# VCO3340_v2.net
KiCad netlist of a schematic drawn in EAGLE
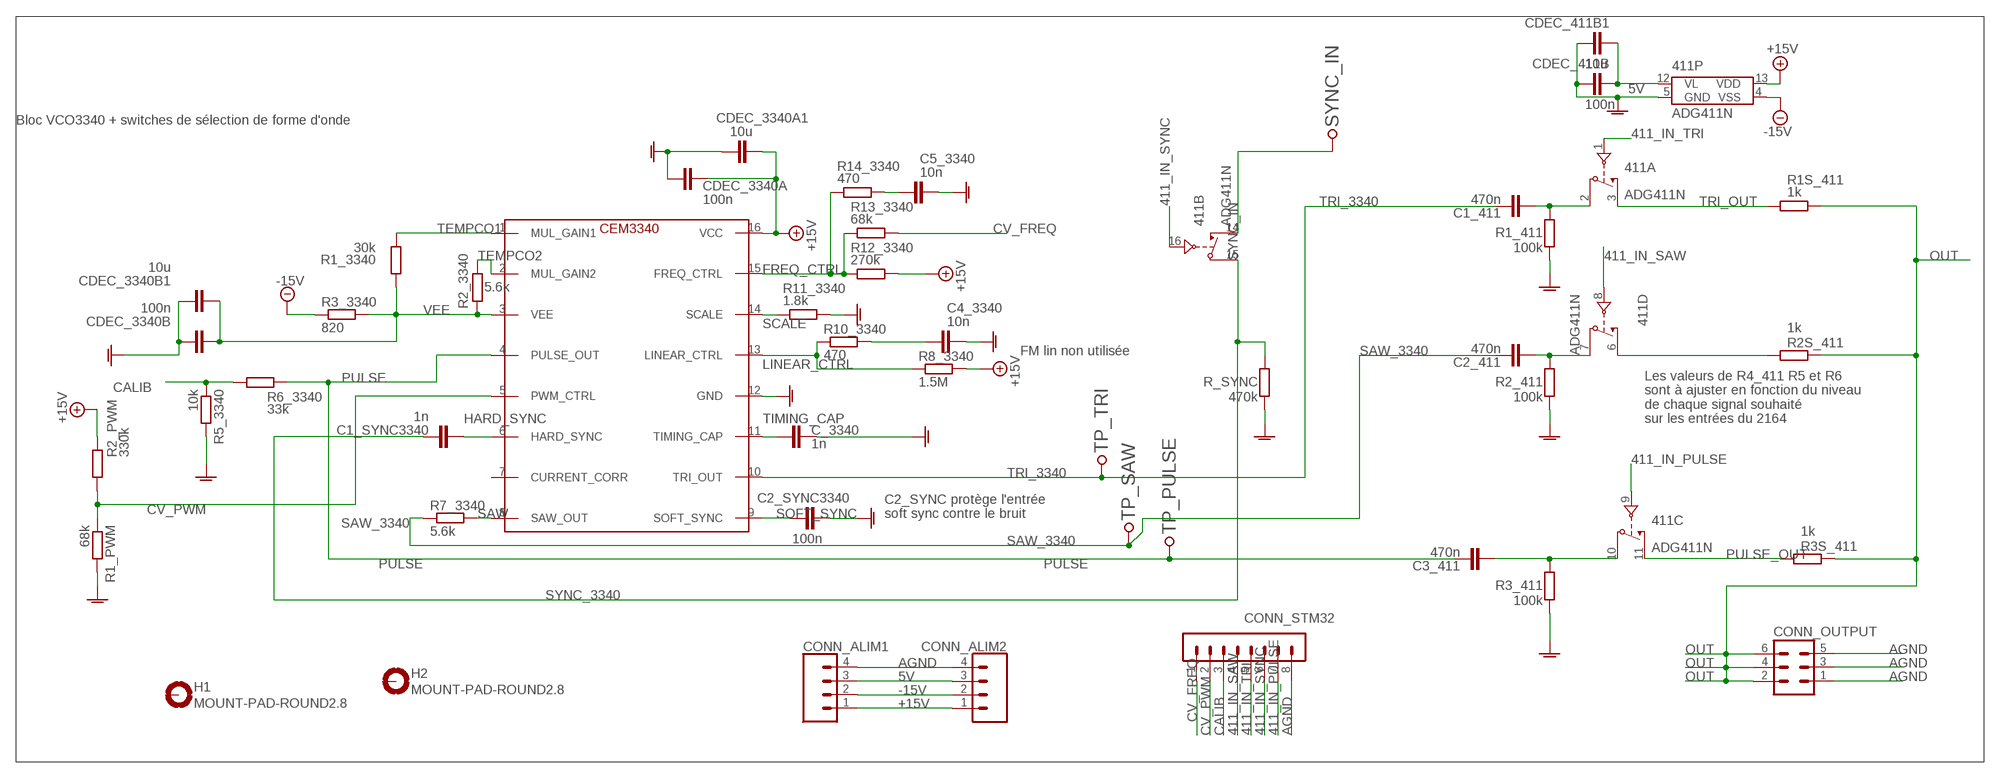
[diagram p0: schematic, sheet 1]

(export (version "E")
  (design (tool "Eeschema 10.0.6"))
  (components
    (comp (ref "411")
      (value "ADG411N")
      (footprint "eagle-import:DIL16")
      (fields (field (name "MF") "ALTERA CORPORATION") (field (name "MPN") "ADG411BN"))
      (libsource (lib "eagle-import") (part "ADG411N"))
    )
    (comp (ref "C1_411")
      (value "470n")
      (footprint "eagle-import:C075-032X103")
      (libsource (lib "eagle-import") (part "C-EU075-032X103"))
    )
    (comp (ref "C1_SYNC3340")
      (value "1n")
      (footprint "eagle-import:C075-032X103")
      (libsource (lib "eagle-import") (part "C-EU075-032X103"))
    )
    (comp (ref "C2_411")
      (value "470n")
      (footprint "eagle-import:C075-032X103")
      (libsource (lib "eagle-import") (part "C-EU075-032X103"))
    )
    (comp (ref "C2_SYNC3340")
      (value "100n")
      (footprint "eagle-import:C075-032X103")
      (libsource (lib "eagle-import") (part "C-EU075-032X103"))
    )
    (comp (ref "C3_411")
      (value "470n")
      (footprint "eagle-import:C102-043X133")
      (libsource (lib "eagle-import") (part "C-EU102-043X133"))
    )
    (comp (ref "C4_3340")
      (value "10n")
      (footprint "eagle-import:C050-025X075")
      (libsource (lib "eagle-import") (part "C-EU050-025X075"))
    )
    (comp (ref "C5_3340")
      (value "10n")
      (footprint "eagle-import:C075-032X103")
      (libsource (lib "eagle-import") (part "C-EU075-032X103"))
    )
    (comp (ref "CDEC_411B")
      (value "100n")
      (footprint "eagle-import:C050-025X075")
      (libsource (lib "eagle-import") (part "C-EU050-025X075"))
    )
    (comp (ref "CDEC_411B1")
      (value "10u")
      (footprint "eagle-import:C050-025X075")
      (libsource (lib "eagle-import") (part "C-EU050-025X075"))
    )
    (comp (ref "CDEC_3340A")
      (value "100n")
      (footprint "eagle-import:C050-025X075")
      (libsource (lib "eagle-import") (part "C-EU050-025X075"))
    )
    (comp (ref "CDEC_3340A1")
      (value "10u")
      (footprint "eagle-import:C050-025X075")
      (libsource (lib "eagle-import") (part "C-EU050-025X075"))
    )
    (comp (ref "CDEC_3340B")
      (value "100n")
      (footprint "eagle-import:C050-025X075")
      (libsource (lib "eagle-import") (part "C-EU050-025X075"))
    )
    (comp (ref "CDEC_3340B1")
      (value "10u")
      (footprint "eagle-import:C050-025X075")
      (libsource (lib "eagle-import") (part "C-EU050-025X075"))
    )
    (comp (ref "CEM3340")
      (value "CEM3340")
      (footprint "eagle-import:DIL16")
      (libsource (lib "eagle-import") (part "CEM3340"))
    )
    (comp (ref "CONN_ALIM1")
      (value "CONN_04")
      (footprint "eagle-import:1X04")
      (libsource (lib "eagle-import") (part "CONN_04"))
    )
    (comp (ref "CONN_ALIM2")
      (value "CONN_04")
      (footprint "eagle-import:1X04")
      (libsource (lib "eagle-import") (part "CONN_04"))
    )
    (comp (ref "CONN_OUTPUT")
      (value "MA03-2")
      (footprint "eagle-import:MA03-2")
      (libsource (lib "eagle-import") (part "MA03-2"))
    )
    (comp (ref "CONN_STM32")
      (value "MA08-1")
      (footprint "eagle-import:MA08-1")
      (libsource (lib "eagle-import") (part "MA08-1"))
    )
    (comp (ref "C_3340")
      (value "1n")
      (footprint "eagle-import:C050-025X075")
      (libsource (lib "eagle-import") (part "C-EU050-025X075"))
    )
    (comp (ref "H1")
      (value "MOUNT-PAD-ROUND2.8")
      (footprint "eagle-import:2,8-PAD")
      (libsource (lib "eagle-import") (part "MOUNT-PAD-ROUND2.8"))
    )
    (comp (ref "H2")
      (value "MOUNT-PAD-ROUND2.8")
      (footprint "eagle-import:2,8-PAD")
      (libsource (lib "eagle-import") (part "MOUNT-PAD-ROUND2.8"))
    )
    (comp (ref "R1S_411")
      (value "1k")
      (footprint "eagle-import:0204_7")
      (libsource (lib "eagle-import") (part "R-EU_0204/7"))
    )
    (comp (ref "R1_411")
      (value "100k")
      (footprint "eagle-import:0207_10")
      (libsource (lib "eagle-import") (part "R-EU_0207/10"))
    )
    (comp (ref "R1_3340")
      (value "30k")
      (footprint "eagle-import:0204_7")
      (libsource (lib "eagle-import") (part "R-EU_0204/7"))
    )
    (comp (ref "R1_PWM")
      (value "68k")
      (footprint "eagle-import:0207_12")
      (libsource (lib "eagle-import") (part "R-EU_0207/12"))
    )
    (comp (ref "R2S_411")
      (value "1k")
      (footprint "eagle-import:0207_10")
      (libsource (lib "eagle-import") (part "R-EU_0207/10"))
    )
    (comp (ref "R2_411")
      (value "100k")
      (footprint "eagle-import:0207_10")
      (libsource (lib "eagle-import") (part "R-EU_0207/10"))
    )
    (comp (ref "R2_3340")
      (value "5.6k")
      (footprint "eagle-import:0204_7")
      (libsource (lib "eagle-import") (part "R-EU_0204/7"))
    )
    (comp (ref "R2_PWM")
      (value "330k")
      (footprint "eagle-import:0204_7")
      (libsource (lib "eagle-import") (part "R-EU_0204/7"))
    )
    (comp (ref "R3S_411")
      (value "1k")
      (footprint "eagle-import:0204_7")
      (libsource (lib "eagle-import") (part "R-EU_0204/7"))
    )
    (comp (ref "R3_411")
      (value "100k")
      (footprint "eagle-import:0204_7")
      (libsource (lib "eagle-import") (part "R-EU_0204/7"))
    )
    (comp (ref "R3_3340")
      (value "820")
      (footprint "eagle-import:0204_7")
      (libsource (lib "eagle-import") (part "R-EU_0204/7"))
    )
    (comp (ref "R5_3340")
      (value "10k")
      (footprint "eagle-import:0204_7")
      (libsource (lib "eagle-import") (part "R-EU_0204/7"))
    )
    (comp (ref "R6_3340")
      (value "33k")
      (footprint "eagle-import:0204_7")
      (libsource (lib "eagle-import") (part "R-EU_0204/7"))
    )
    (comp (ref "R7_3340")
      (value "5.6k")
      (footprint "eagle-import:0207_10")
      (libsource (lib "eagle-import") (part "R-EU_0207/10"))
    )
    (comp (ref "R8_3340")
      (value "1.5M")
      (footprint "eagle-import:0204_7")
      (libsource (lib "eagle-import") (part "R-EU_0204/7"))
    )
    (comp (ref "R10_3340")
      (value "470")
      (footprint "eagle-import:0204_7")
      (libsource (lib "eagle-import") (part "R-EU_0204/7"))
    )
    (comp (ref "R11_3340")
      (value "1.8k")
      (footprint "eagle-import:0204_7")
      (libsource (lib "eagle-import") (part "R-EU_0204/7"))
    )
    (comp (ref "R12_3340")
      (value "270k")
      (footprint "eagle-import:0204_7")
      (libsource (lib "eagle-import") (part "R-EU_0204/7"))
    )
    (comp (ref "R13_3340")
      (value "68k")
      (footprint "eagle-import:0204_7")
      (libsource (lib "eagle-import") (part "R-EU_0204/7"))
    )
    (comp (ref "R14_3340")
      (value "470")
      (footprint "eagle-import:0204_7")
      (libsource (lib "eagle-import") (part "R-EU_0204/7"))
    )
    (comp (ref "R_SYNC")
      (value "470k")
      (footprint "eagle-import:0204_7")
      (libsource (lib "eagle-import") (part "R-EU_0204/7"))
    )
    (comp (ref "SYNC_IN")
      (value "TESTPOINT")
      (footprint "eagle-import:TESTPOINT_63")
      (libsource (lib "eagle-import") (part "TESTPOINT"))
    )
    (comp (ref "TP_PULSE")
      (value "TESTPOINT")
      (footprint "eagle-import:TESTPOINT_63")
      (libsource (lib "eagle-import") (part "TESTPOINT"))
    )
    (comp (ref "TP_SAW")
      (value "TESTPOINT")
      (footprint "eagle-import:TESTPOINT_63")
      (libsource (lib "eagle-import") (part "TESTPOINT"))
    )
    (comp (ref "TP_TRI")
      (value "TESTPOINT")
      (footprint "eagle-import:TESTPOINT_63")
      (libsource (lib "eagle-import") (part "TESTPOINT"))
    )
  )
  (nets
    (net (code "1") (name "+15V") (class "Default")
      (node (ref "411") (pin "13") (pinfunction "VDD_13") (pintype "power_in"))
      (node (ref "CDEC_3340A") (pin "2") (pinfunction "2_2") (pintype "passive"))
      (node (ref "CDEC_3340A1") (pin "2") (pinfunction "2_2") (pintype "passive"))
      (node (ref "CEM3340") (pin "16") (pinfunction "VCC_16") (pintype "bidirectional"))
      (node (ref "CONN_ALIM1") (pin "1") (pinfunction "1_1") (pintype "passive"))
      (node (ref "CONN_ALIM2") (pin "1") (pinfunction "1_1") (pintype "passive"))
      (node (ref "R12_3340") (pin "2") (pinfunction "2_2") (pintype "passive"))
      (node (ref "R2_PWM") (pin "2") (pinfunction "2_2") (pintype "passive"))
      (node (ref "R8_3340") (pin "2") (pinfunction "2_2") (pintype "passive"))
    )
    (net (code "2") (name "-15V") (class "Default")
      (node (ref "411") (pin "4") (pinfunction "VSS_4") (pintype "power_in"))
      (node (ref "CONN_ALIM1") (pin "2") (pinfunction "2_2") (pintype "passive"))
      (node (ref "CONN_ALIM2") (pin "2") (pinfunction "2_2") (pintype "passive"))
      (node (ref "R3_3340") (pin "1") (pinfunction "1_1") (pintype "passive"))
    )
    (net (code "3") (name "/5V") (class "Default")
      (node (ref "411") (pin "12") (pinfunction "VL_12") (pintype "power_in"))
      (node (ref "CDEC_411B") (pin "1") (pinfunction "1_1") (pintype "passive"))
      (node (ref "CDEC_411B1") (pin "1") (pinfunction "1_1") (pintype "passive"))
      (node (ref "CONN_ALIM1") (pin "3") (pinfunction "3_3") (pintype "passive"))
      (node (ref "CONN_ALIM2") (pin "3") (pinfunction "3_3") (pintype "passive"))
    )
    (net (code "4") (name "/411_IN_PULSE") (class "Default")
      (node (ref "411") (pin "9") (pinfunction "IN_9") (pintype "input"))
      (node (ref "CONN_STM32") (pin "7") (pinfunction "7_7") (pintype "passive"))
    )
    (net (code "5") (name "/411_IN_SAW") (class "Default")
      (node (ref "411") (pin "8") (pinfunction "IN_8") (pintype "input"))
      (node (ref "CONN_STM32") (pin "4") (pinfunction "4_4") (pintype "passive"))
    )
    (net (code "6") (name "/411_IN_SYNC") (class "Default")
      (node (ref "411") (pin "16") (pinfunction "IN_16") (pintype "input"))
      (node (ref "CONN_STM32") (pin "6") (pinfunction "6_6") (pintype "passive"))
    )
    (net (code "7") (name "/411_IN_TRI") (class "Default")
      (node (ref "411") (pin "1") (pinfunction "IN_1") (pintype "input"))
      (node (ref "CONN_STM32") (pin "5") (pinfunction "5_5") (pintype "passive"))
    )
    (net (code "8") (name "/CALIB") (class "Default")
      (node (ref "CONN_STM32") (pin "3") (pinfunction "3_3") (pintype "passive"))
      (node (ref "R5_3340") (pin "1") (pinfunction "1_1") (pintype "passive"))
      (node (ref "R6_3340") (pin "1") (pinfunction "1_1") (pintype "passive"))
    )
    (net (code "9") (name "/CV_FREQ") (class "Default")
      (node (ref "CONN_STM32") (pin "1") (pinfunction "1_1") (pintype "passive"))
      (node (ref "R13_3340") (pin "2") (pinfunction "2_2") (pintype "passive"))
    )
    (net (code "10") (name "/CV_PWM") (class "Default")
      (node (ref "CEM3340") (pin "5") (pinfunction "PWM_CTRL_5") (pintype "bidirectional"))
      (node (ref "CONN_STM32") (pin "2") (pinfunction "2_2") (pintype "passive"))
      (node (ref "R1_PWM") (pin "1") (pinfunction "1_1") (pintype "passive"))
      (node (ref "R2_PWM") (pin "1") (pinfunction "1_1") (pintype "passive"))
    )
    (net (code "11") (name "/FREQ_CTRL") (class "Default")
      (node (ref "CEM3340") (pin "15") (pinfunction "FREQ_CTRL_15") (pintype "bidirectional"))
      (node (ref "R12_3340") (pin "1") (pinfunction "1_1") (pintype "passive"))
      (node (ref "R13_3340") (pin "1") (pinfunction "1_1") (pintype "passive"))
      (node (ref "R14_3340") (pin "1") (pinfunction "1_1") (pintype "passive"))
    )
    (net (code "12") (name "/HARD_SYNC") (class "Default")
      (node (ref "C1_SYNC3340") (pin "2") (pinfunction "2_2") (pintype "passive"))
      (node (ref "CEM3340") (pin "6") (pinfunction "HARD_SYNC_6") (pintype "bidirectional"))
    )
    (net (code "13") (name "/LINEAR_CTRL") (class "Default")
      (node (ref "CEM3340") (pin "13") (pinfunction "LINEAR_CTRL_13") (pintype "bidirectional"))
      (node (ref "R10_3340") (pin "1") (pinfunction "1_1") (pintype "passive"))
      (node (ref "R8_3340") (pin "1") (pinfunction "1_1") (pintype "passive"))
    )
    (net (code "14") (name "/OUT") (class "Default")
      (node (ref "CONN_OUTPUT") (pin "2") (pinfunction "2_2") (pintype "passive"))
      (node (ref "CONN_OUTPUT") (pin "4") (pinfunction "4_4") (pintype "passive"))
      (node (ref "CONN_OUTPUT") (pin "6") (pinfunction "6_6") (pintype "passive"))
      (node (ref "R1S_411") (pin "2") (pinfunction "2_2") (pintype "passive"))
      (node (ref "R2S_411") (pin "1") (pinfunction "1_1") (pintype "passive"))
      (node (ref "R3S_411") (pin "1") (pinfunction "1_1") (pintype "passive"))
    )
    (net (code "15") (name "/PULSE") (class "Default")
      (node (ref "C3_411") (pin "1") (pinfunction "1_1") (pintype "passive"))
      (node (ref "CEM3340") (pin "4") (pinfunction "PULSE_OUT_4") (pintype "bidirectional"))
      (node (ref "R6_3340") (pin "2") (pinfunction "2_2") (pintype "passive"))
      (node (ref "TP_PULSE") (pin "P$1") (pinfunction "P$1_P$1") (pintype "passive"))
    )
    (net (code "16") (name "/PULSE_OUT") (class "Default")
      (node (ref "411") (pin "11") (pinfunction "S_11") (pintype "passive"))
      (node (ref "R3S_411") (pin "2") (pinfunction "2_2") (pintype "passive"))
    )
    (net (code "17") (name "/SAW") (class "Default")
      (node (ref "CEM3340") (pin "8") (pinfunction "SAW_OUT_8") (pintype "bidirectional"))
      (node (ref "R7_3340") (pin "2") (pinfunction "2_2") (pintype "passive"))
    )
    (net (code "18") (name "/SAW_3340") (class "Default")
      (node (ref "C2_411") (pin "1") (pinfunction "1_1") (pintype "passive"))
      (node (ref "R7_3340") (pin "1") (pinfunction "1_1") (pintype "passive"))
      (node (ref "TP_SAW") (pin "P$1") (pinfunction "P$1_P$1") (pintype "passive"))
    )
    (net (code "19") (name "/SCALE") (class "Default")
      (node (ref "CEM3340") (pin "14") (pinfunction "SCALE_14") (pintype "bidirectional"))
      (node (ref "R11_3340") (pin "1") (pinfunction "1_1") (pintype "passive"))
    )
    (net (code "20") (name "/SOFT_SYNC") (class "Default")
      (node (ref "C2_SYNC3340") (pin "2") (pinfunction "2_2") (pintype "passive"))
      (node (ref "CEM3340") (pin "9") (pinfunction "SOFT_SYNC_9") (pintype "bidirectional"))
    )
    (net (code "21") (name "/SYNC_3340") (class "Default")
      (node (ref "411") (pin "15") (pinfunction "D_15") (pintype "passive"))
      (node (ref "C1_SYNC3340") (pin "1") (pinfunction "1_1") (pintype "passive"))
      (node (ref "R_SYNC") (pin "2") (pinfunction "2_2") (pintype "passive"))
    )
    (net (code "22") (name "/SYNC_IN") (class "Default")
      (node (ref "411") (pin "14") (pinfunction "S_14") (pintype "passive"))
      (node (ref "SYNC_IN") (pin "P$1") (pinfunction "P$1_P$1") (pintype "passive"))
    )
    (net (code "23") (name "/TEMPCO1") (class "Default")
      (node (ref "CEM3340") (pin "1") (pinfunction "MUL_GAIN1_1") (pintype "bidirectional"))
      (node (ref "R1_3340") (pin "1") (pinfunction "1_1") (pintype "passive"))
    )
    (net (code "24") (name "/TEMPCO2") (class "Default")
      (node (ref "CEM3340") (pin "2") (pinfunction "MUL_GAIN2_2") (pintype "bidirectional"))
      (node (ref "R2_3340") (pin "1") (pinfunction "1_1") (pintype "passive"))
    )
    (net (code "25") (name "/TIMING_CAP") (class "Default")
      (node (ref "CEM3340") (pin "11") (pinfunction "TIMING_CAP_11") (pintype "bidirectional"))
      (node (ref "C_3340") (pin "2") (pinfunction "2_2") (pintype "passive"))
    )
    (net (code "26") (name "/TRI_3340") (class "Default")
      (node (ref "C1_411") (pin "1") (pinfunction "1_1") (pintype "passive"))
      (node (ref "CEM3340") (pin "10") (pinfunction "TRI_OUT_10") (pintype "bidirectional"))
      (node (ref "TP_TRI") (pin "P$1") (pinfunction "P$1_P$1") (pintype "passive"))
    )
    (net (code "27") (name "/TRI_OUT") (class "Default")
      (node (ref "411") (pin "3") (pinfunction "S_3") (pintype "passive"))
      (node (ref "R1S_411") (pin "1") (pinfunction "1_1") (pintype "passive"))
    )
    (net (code "28") (name "/VEE") (class "Default")
      (node (ref "CDEC_3340B") (pin "2") (pinfunction "2_2") (pintype "passive"))
      (node (ref "CDEC_3340B1") (pin "2") (pinfunction "2_2") (pintype "passive"))
      (node (ref "CEM3340") (pin "3") (pinfunction "VEE_3") (pintype "bidirectional"))
      (node (ref "R1_3340") (pin "2") (pinfunction "2_2") (pintype "passive"))
      (node (ref "R2_3340") (pin "2") (pinfunction "2_2") (pintype "passive"))
      (node (ref "R3_3340") (pin "2") (pinfunction "2_2") (pintype "passive"))
    )
    (net (code "29") (name "AGND") (class "Default")
      (node (ref "411") (pin "5") (pinfunction "GND_5") (pintype "power_in"))
      (node (ref "C2_SYNC3340") (pin "1") (pinfunction "1_1") (pintype "passive"))
      (node (ref "C4_3340") (pin "2") (pinfunction "2_2") (pintype "passive"))
      (node (ref "C5_3340") (pin "1") (pinfunction "1_1") (pintype "passive"))
      (node (ref "CDEC_3340A") (pin "1") (pinfunction "1_1") (pintype "passive"))
      (node (ref "CDEC_3340A1") (pin "1") (pinfunction "1_1") (pintype "passive"))
      (node (ref "CDEC_3340B") (pin "1") (pinfunction "1_1") (pintype "passive"))
      (node (ref "CDEC_3340B1") (pin "1") (pinfunction "1_1") (pintype "passive"))
      (node (ref "CDEC_411B") (pin "2") (pinfunction "2_2") (pintype "passive"))
      (node (ref "CDEC_411B1") (pin "2") (pinfunction "2_2") (pintype "passive"))
      (node (ref "CEM3340") (pin "12") (pinfunction "GND_12") (pintype "bidirectional"))
      (node (ref "CONN_ALIM1") (pin "4") (pinfunction "4_4") (pintype "passive"))
      (node (ref "CONN_ALIM2") (pin "4") (pinfunction "4_4") (pintype "passive"))
      (node (ref "CONN_OUTPUT") (pin "1") (pinfunction "1_1") (pintype "passive"))
      (node (ref "CONN_OUTPUT") (pin "3") (pinfunction "3_3") (pintype "passive"))
      (node (ref "CONN_OUTPUT") (pin "5") (pinfunction "5_5") (pintype "passive"))
      (node (ref "CONN_STM32") (pin "8") (pinfunction "8_8") (pintype "passive"))
      (node (ref "C_3340") (pin "1") (pinfunction "1_1") (pintype "passive"))
      (node (ref "R11_3340") (pin "2") (pinfunction "2_2") (pintype "passive"))
      (node (ref "R1_411") (pin "1") (pinfunction "1_1") (pintype "passive"))
      (node (ref "R1_PWM") (pin "2") (pinfunction "2_2") (pintype "passive"))
      (node (ref "R2_411") (pin "1") (pinfunction "1_1") (pintype "passive"))
      (node (ref "R3_411") (pin "1") (pinfunction "1_1") (pintype "passive"))
      (node (ref "R5_3340") (pin "2") (pinfunction "2_2") (pintype "passive"))
      (node (ref "R_SYNC") (pin "1") (pinfunction "1_1") (pintype "passive"))
    )
    (net (code "30") (name "Net-(411A-D)") (class "Default")
      (node (ref "411") (pin "2") (pinfunction "D_2") (pintype "passive"))
      (node (ref "C1_411") (pin "2") (pinfunction "2_2") (pintype "passive"))
      (node (ref "R1_411") (pin "2") (pinfunction "2_2") (pintype "passive"))
    )
    (net (code "31") (name "Net-(411C-D)") (class "Default")
      (node (ref "411") (pin "10") (pinfunction "D_10") (pintype "passive"))
      (node (ref "C3_411") (pin "2") (pinfunction "2_2") (pintype "passive"))
      (node (ref "R3_411") (pin "2") (pinfunction "2_2") (pintype "passive"))
    )
    (net (code "32") (name "Net-(411D-D)") (class "Default")
      (node (ref "411") (pin "7") (pinfunction "D_7") (pintype "passive"))
      (node (ref "C2_411") (pin "2") (pinfunction "2_2") (pintype "passive"))
      (node (ref "R2_411") (pin "2") (pinfunction "2_2") (pintype "passive"))
    )
    (net (code "33") (name "Net-(411D-S)") (class "Default")
      (node (ref "411") (pin "6") (pinfunction "S_6") (pintype "passive"))
      (node (ref "R2S_411") (pin "2") (pinfunction "2_2") (pintype "passive"))
    )
    (net (code "34") (name "Net-(C4_3340-Pad1)") (class "Default")
      (node (ref "C4_3340") (pin "1") (pinfunction "1_1") (pintype "passive"))
      (node (ref "R10_3340") (pin "2") (pinfunction "2_2") (pintype "passive"))
    )
    (net (code "35") (name "Net-(C5_3340-Pad2)") (class "Default")
      (node (ref "C5_3340") (pin "2") (pinfunction "2_2") (pintype "passive"))
      (node (ref "R14_3340") (pin "2") (pinfunction "2_2") (pintype "passive"))
    )
    (net (code "36") (name "unconnected-(CEM3340-CURRENT_CORR-Pad7)") (class "Default")
      (node (ref "CEM3340") (pin "7") (pinfunction "CURRENT_CORR_7") (pintype "bidirectional"))
    )
    (net (code "37") (name "unconnected-(H1-MOUNT-PadB2,8)") (class "Default")
      (node (ref "H1") (pin "B2,8") (pinfunction "MOUNT_B2,8") (pintype "passive"))
    )
    (net (code "38") (name "unconnected-(H2-MOUNT-PadB2,8)") (class "Default")
      (node (ref "H2") (pin "B2,8") (pinfunction "MOUNT_B2,8") (pintype "passive"))
    )
  )
)
